# Beunboard_rev1.net
KiCad netlist of a schematic drawn in EAGLE
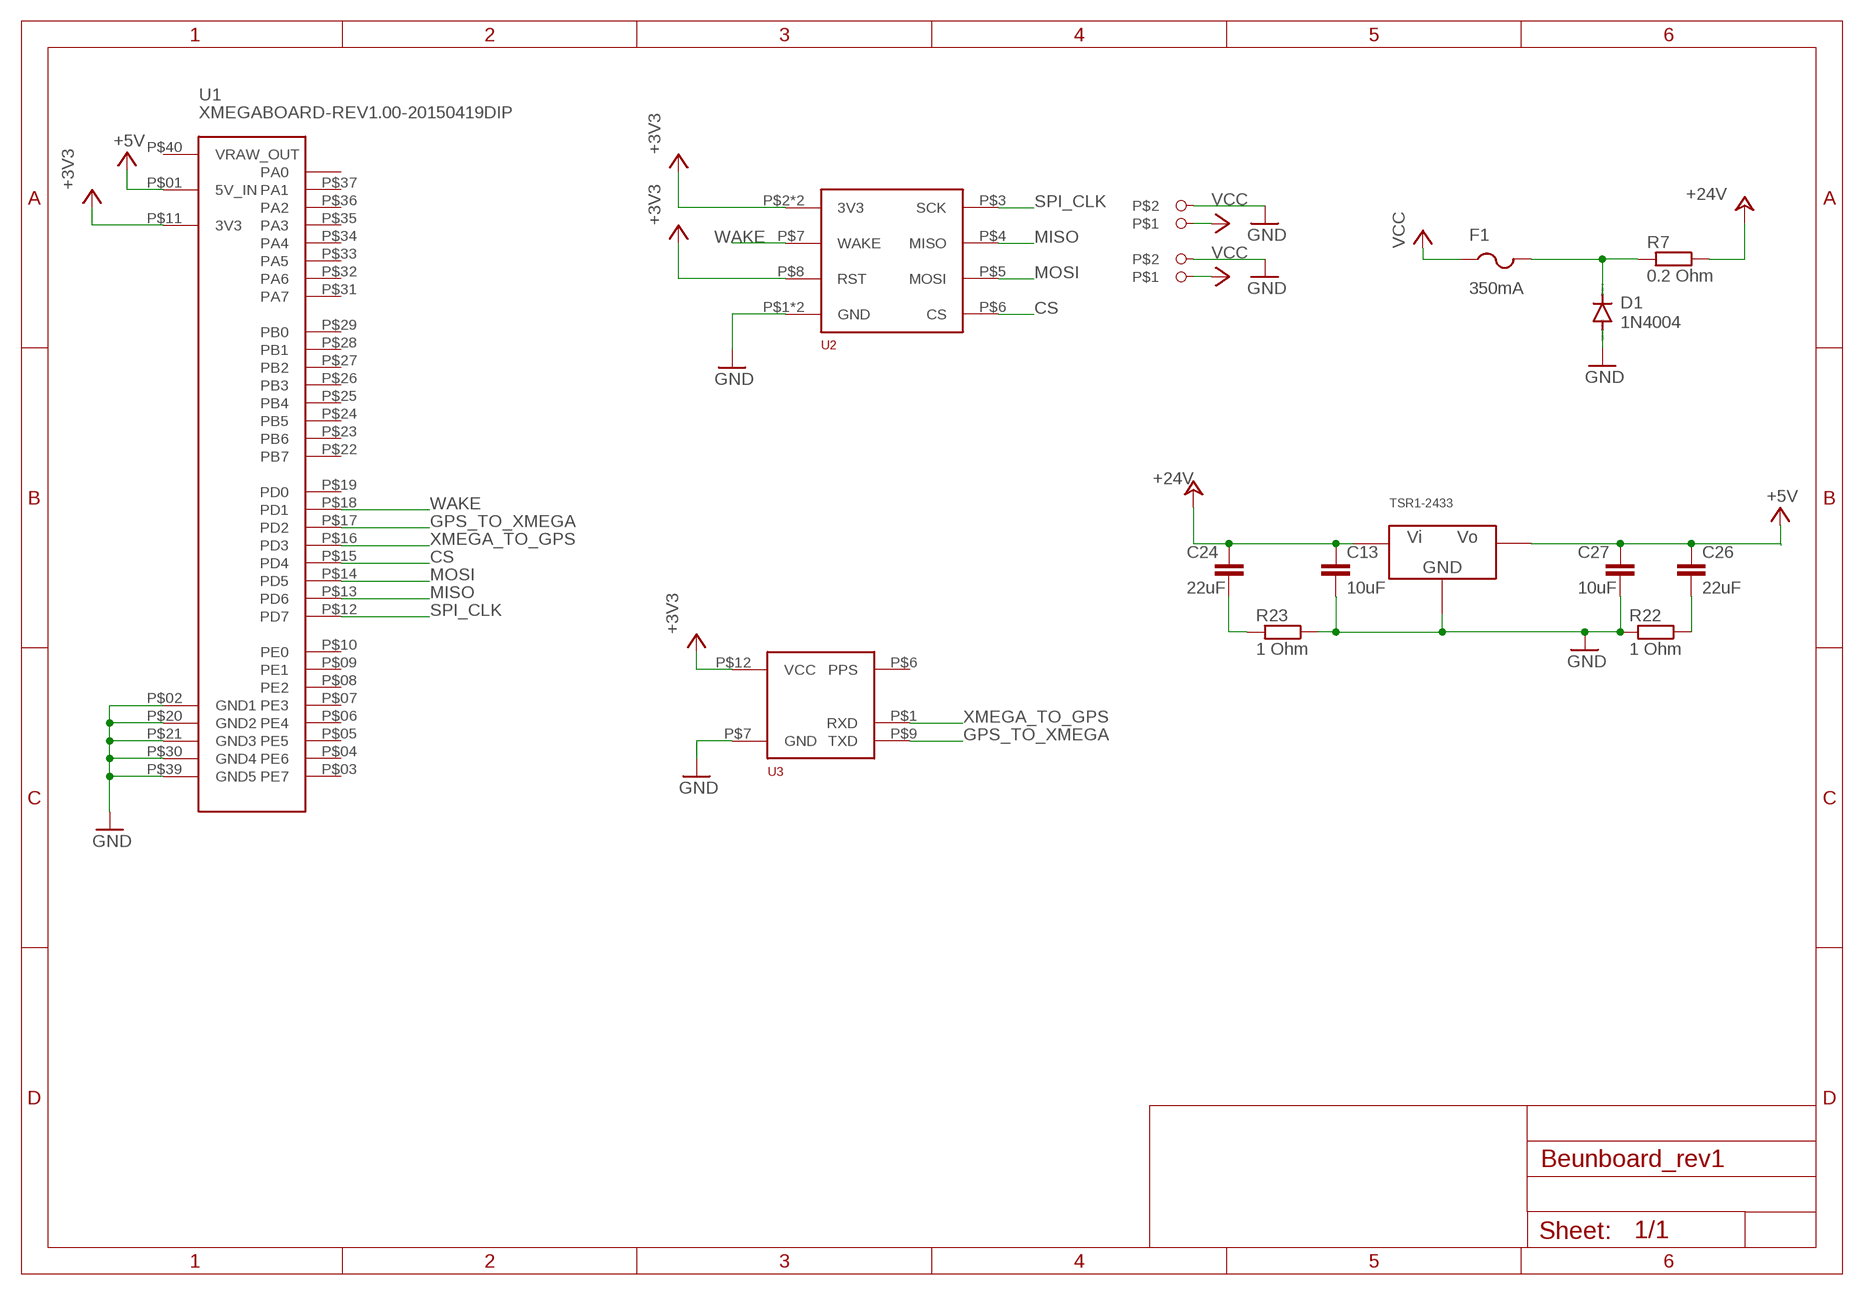
[diagram p0: schematic, sheet 1]

(export (version "E")
  (design (tool "Eeschema 10.0.6"))
  (components
    (comp (ref "C13")
      (value "10uF")
      (footprint "eagle-import:C1206")
      (libsource (lib "eagle-import") (part "C-EUC1206"))
    )
    (comp (ref "C24")
      (value "22uF")
      (footprint "eagle-import:C1206")
      (libsource (lib "eagle-import") (part "C-EUC1206"))
    )
    (comp (ref "C26")
      (value "22uF")
      (footprint "eagle-import:C1206")
      (libsource (lib "eagle-import") (part "C-EUC1206"))
    )
    (comp (ref "C27")
      (value "10uF")
      (footprint "eagle-import:C1206")
      (libsource (lib "eagle-import") (part "C-EUC1206"))
    )
    (comp (ref "D1")
      (value "1N4004")
      (footprint "eagle-import:DO41-10")
      (libsource (lib "eagle-import") (part "1N4004"))
    )
    (comp (ref "F1")
      (value "350mA")
      (footprint "eagle-import:R1206")
      (libsource (lib "eagle-import") (part "PTCFUSE-1206"))
    )
    (comp (ref "POWER1")
      (value "CON_3.81MM2_SIDE")
      (footprint "eagle-import:CON_3.81MM2_SIDE")
      (libsource (lib "eagle-import") (part "CON_3.81MM2_SIDE"))
    )
    (comp (ref "POWER2")
      (value "CON_3.81MM2_SIDE")
      (footprint "eagle-import:CON_3.81MM2_SIDE")
      (libsource (lib "eagle-import") (part "CON_3.81MM2_SIDE"))
    )
    (comp (ref "R7")
      (value "0.2 Ohm")
      (footprint "eagle-import:R0805")
      (libsource (lib "eagle-import") (part "R-EU_R0805"))
    )
    (comp (ref "R22")
      (value "1 Ohm")
      (footprint "eagle-import:R0805")
      (libsource (lib "eagle-import") (part "R-EU_R0805"))
    )
    (comp (ref "R23")
      (value "1 Ohm")
      (footprint "eagle-import:R0805")
      (libsource (lib "eagle-import") (part "R-EU_R0805"))
    )
    (comp (ref "TSR1-2433")
      (value "TSR1-2433")
      (footprint "eagle-import:TSR1-2433")
      (libsource (lib "eagle-import") (part "TSR1-2433"))
    )
    (comp (ref "U1")
      (value "XMEGABOARD-REV1.00-20150419DIP")
      (footprint "eagle-import:XMEGABOARD-REV1.00-20150419")
      (libsource (lib "eagle-import") (part "XMEGABOARD-REV1.00-20150419DIP"))
    )
    (comp (ref "U2")
      (value "SPARKFUN_BNO080SPARKFUN_BNO080")
      (footprint "eagle-import:SPARKFUN_BNO080")
      (libsource (lib "eagle-import") (part "SPARKFUN_BNO080SPARKFUN_BNO080"))
    )
    (comp (ref "U3")
      (value "NAVSPARK_MININAVSPARK_MINI")
      (footprint "eagle-import:NAVSPARK_MINI")
      (libsource (lib "eagle-import") (part "NAVSPARK_MININAVSPARK_MINI"))
    )
  )
  (nets
    (net (code "1") (name "+3V3") (class "Default")
      (node (ref "U1") (pin "P$11") (pinfunction "3V3_P$11") (pintype "bidirectional"))
      (node (ref "U2") (pin "P$18") (pinfunction "3V3_P$18") (pintype "bidirectional"))
      (node (ref "U2") (pin "P$2") (pinfunction "3V3_P$2") (pintype "bidirectional"))
      (node (ref "U2") (pin "P$8") (pinfunction "RST_P$8") (pintype "bidirectional"))
      (node (ref "U3") (pin "P$12") (pinfunction "VCC_P$12") (pintype "bidirectional"))
    )
    (net (code "2") (name "+5V") (class "Default")
      (node (ref "C26") (pin "1") (pinfunction "1_1") (pintype "passive"))
      (node (ref "C27") (pin "1") (pinfunction "1_1") (pintype "passive"))
      (node (ref "TSR1-2433") (pin "VO") (pinfunction "VO_VO") (pintype "bidirectional"))
      (node (ref "U1") (pin "P$01") (pinfunction "5V_IN_P$01") (pintype "bidirectional"))
    )
    (net (code "3") (name "+24V") (class "Default")
      (node (ref "C13") (pin "1") (pinfunction "1_1") (pintype "passive"))
      (node (ref "C24") (pin "1") (pinfunction "1_1") (pintype "passive"))
      (node (ref "R7") (pin "1") (pinfunction "1_1") (pintype "passive"))
      (node (ref "TSR1-2433") (pin "VI") (pinfunction "VI_VI") (pintype "bidirectional"))
    )
    (net (code "4") (name "/CS") (class "Default")
      (node (ref "U1") (pin "P$15") (pinfunction "PD4_P$15") (pintype "bidirectional"))
      (node (ref "U2") (pin "P$6") (pinfunction "CS_P$6") (pintype "bidirectional"))
    )
    (net (code "5") (name "/GPS_TO_XMEGA") (class "Default")
      (node (ref "U1") (pin "P$17") (pinfunction "PD2_P$17") (pintype "bidirectional"))
      (node (ref "U3") (pin "P$9") (pinfunction "TXD_P$9") (pintype "bidirectional"))
    )
    (net (code "6") (name "/MISO") (class "Default")
      (node (ref "U1") (pin "P$13") (pinfunction "PD6_P$13") (pintype "bidirectional"))
      (node (ref "U2") (pin "P$4") (pinfunction "MISO_P$4") (pintype "bidirectional"))
    )
    (net (code "7") (name "/MOSI") (class "Default")
      (node (ref "U1") (pin "P$14") (pinfunction "PD5_P$14") (pintype "bidirectional"))
      (node (ref "U2") (pin "P$5") (pinfunction "MOSI_P$5") (pintype "bidirectional"))
    )
    (net (code "8") (name "/SPI_CLK") (class "Default")
      (node (ref "U1") (pin "P$12") (pinfunction "PD7_P$12") (pintype "bidirectional"))
      (node (ref "U2") (pin "P$3") (pinfunction "SCK_P$3") (pintype "bidirectional"))
    )
    (net (code "9") (name "/WAKE") (class "Default")
      (node (ref "U1") (pin "P$18") (pinfunction "PD1_P$18") (pintype "bidirectional"))
      (node (ref "U2") (pin "P$7") (pinfunction "WAKE_P$7") (pintype "bidirectional"))
    )
    (net (code "10") (name "/XMEGA_TO_GPS") (class "Default")
      (node (ref "U1") (pin "P$16") (pinfunction "PD3_P$16") (pintype "bidirectional"))
      (node (ref "U3") (pin "P$1") (pinfunction "RXD_P$1") (pintype "bidirectional"))
    )
    (net (code "11") (name "GND") (class "Default")
      (node (ref "C13") (pin "2") (pinfunction "2_2") (pintype "passive"))
      (node (ref "C27") (pin "2") (pinfunction "2_2") (pintype "passive"))
      (node (ref "D1") (pin "A") (pinfunction "A_A") (pintype "passive"))
      (node (ref "POWER1") (pin "P$2") (pinfunction "P$2_P$2") (pintype "bidirectional"))
      (node (ref "POWER2") (pin "P$2") (pinfunction "P$2_P$2") (pintype "bidirectional"))
      (node (ref "R22") (pin "2") (pinfunction "2_2") (pintype "passive"))
      (node (ref "R23") (pin "1") (pinfunction "1_1") (pintype "passive"))
      (node (ref "TSR1-2433") (pin "GND") (pinfunction "GND_GND") (pintype "bidirectional"))
      (node (ref "U1") (pin "P$02") (pinfunction "GND1_P$02") (pintype "bidirectional"))
      (node (ref "U1") (pin "P$20") (pinfunction "GND2_P$20") (pintype "bidirectional"))
      (node (ref "U1") (pin "P$21") (pinfunction "GND3_P$21") (pintype "bidirectional"))
      (node (ref "U1") (pin "P$30") (pinfunction "GND4_P$30") (pintype "bidirectional"))
      (node (ref "U1") (pin "P$39") (pinfunction "GND5_P$39") (pintype "bidirectional"))
      (node (ref "U2") (pin "P$1") (pinfunction "GND_P$1") (pintype "bidirectional"))
      (node (ref "U2") (pin "P$17") (pinfunction "GND_P$17") (pintype "bidirectional"))
      (node (ref "U3") (pin "P$7") (pinfunction "GND_P$7") (pintype "bidirectional"))
    )
    (net (code "12") (name "Net-(C24-Pad2)") (class "Default")
      (node (ref "C24") (pin "2") (pinfunction "2_2") (pintype "passive"))
      (node (ref "R23") (pin "2") (pinfunction "2_2") (pintype "passive"))
    )
    (net (code "13") (name "Net-(C26-Pad2)") (class "Default")
      (node (ref "C26") (pin "2") (pinfunction "2_2") (pintype "passive"))
      (node (ref "R22") (pin "1") (pinfunction "1_1") (pintype "passive"))
    )
    (net (code "14") (name "Net-(D1-PadC)") (class "Default")
      (node (ref "D1") (pin "C") (pinfunction "C_C") (pintype "passive"))
      (node (ref "F1") (pin "2") (pinfunction "2_2") (pintype "passive"))
      (node (ref "R7") (pin "2") (pinfunction "2_2") (pintype "passive"))
    )
    (net (code "15") (name "VCC") (class "Default")
      (node (ref "F1") (pin "1") (pinfunction "1_1") (pintype "passive"))
      (node (ref "POWER1") (pin "P$1") (pinfunction "P$1_P$1") (pintype "bidirectional"))
      (node (ref "POWER2") (pin "P$1") (pinfunction "P$1_P$1") (pintype "bidirectional"))
    )
    (net (code "16") (name "unconnected-(U1-PA0-PadP$38)") (class "Default")
      (node (ref "U1") (pin "P$38") (pinfunction "PA0_P$38") (pintype "bidirectional"))
    )
    (net (code "17") (name "unconnected-(U1-PA1-PadP$37)") (class "Default")
      (node (ref "U1") (pin "P$37") (pinfunction "PA1_P$37") (pintype "bidirectional"))
    )
    (net (code "18") (name "unconnected-(U1-PA2-PadP$36)") (class "Default")
      (node (ref "U1") (pin "P$36") (pinfunction "PA2_P$36") (pintype "bidirectional"))
    )
    (net (code "19") (name "unconnected-(U1-PA3-PadP$35)") (class "Default")
      (node (ref "U1") (pin "P$35") (pinfunction "PA3_P$35") (pintype "bidirectional"))
    )
    (net (code "20") (name "unconnected-(U1-PA4-PadP$34)") (class "Default")
      (node (ref "U1") (pin "P$34") (pinfunction "PA4_P$34") (pintype "bidirectional"))
    )
    (net (code "21") (name "unconnected-(U1-PA5-PadP$33)") (class "Default")
      (node (ref "U1") (pin "P$33") (pinfunction "PA5_P$33") (pintype "bidirectional"))
    )
    (net (code "22") (name "unconnected-(U1-PA6-PadP$32)") (class "Default")
      (node (ref "U1") (pin "P$32") (pinfunction "PA6_P$32") (pintype "bidirectional"))
    )
    (net (code "23") (name "unconnected-(U1-PA7-PadP$31)") (class "Default")
      (node (ref "U1") (pin "P$31") (pinfunction "PA7_P$31") (pintype "bidirectional"))
    )
    (net (code "24") (name "unconnected-(U1-PB0-PadP$29)") (class "Default")
      (node (ref "U1") (pin "P$29") (pinfunction "PB0_P$29") (pintype "bidirectional"))
    )
    (net (code "25") (name "unconnected-(U1-PB1-PadP$28)") (class "Default")
      (node (ref "U1") (pin "P$28") (pinfunction "PB1_P$28") (pintype "bidirectional"))
    )
    (net (code "26") (name "unconnected-(U1-PB2-PadP$27)") (class "Default")
      (node (ref "U1") (pin "P$27") (pinfunction "PB2_P$27") (pintype "bidirectional"))
    )
    (net (code "27") (name "unconnected-(U1-PB3-PadP$26)") (class "Default")
      (node (ref "U1") (pin "P$26") (pinfunction "PB3_P$26") (pintype "bidirectional"))
    )
    (net (code "28") (name "unconnected-(U1-PB4-PadP$25)") (class "Default")
      (node (ref "U1") (pin "P$25") (pinfunction "PB4_P$25") (pintype "bidirectional"))
    )
    (net (code "29") (name "unconnected-(U1-PB5-PadP$24)") (class "Default")
      (node (ref "U1") (pin "P$24") (pinfunction "PB5_P$24") (pintype "bidirectional"))
    )
    (net (code "30") (name "unconnected-(U1-PB6-PadP$23)") (class "Default")
      (node (ref "U1") (pin "P$23") (pinfunction "PB6_P$23") (pintype "bidirectional"))
    )
    (net (code "31") (name "unconnected-(U1-PB7-PadP$22)") (class "Default")
      (node (ref "U1") (pin "P$22") (pinfunction "PB7_P$22") (pintype "bidirectional"))
    )
    (net (code "32") (name "unconnected-(U1-PD0-PadP$19)") (class "Default")
      (node (ref "U1") (pin "P$19") (pinfunction "PD0_P$19") (pintype "bidirectional"))
    )
    (net (code "33") (name "unconnected-(U1-PE0-PadP$10)") (class "Default")
      (node (ref "U1") (pin "P$10") (pinfunction "PE0_P$10") (pintype "bidirectional"))
    )
    (net (code "34") (name "unconnected-(U1-PE1-PadP$09)") (class "Default")
      (node (ref "U1") (pin "P$09") (pinfunction "PE1_P$09") (pintype "bidirectional"))
    )
    (net (code "35") (name "unconnected-(U1-PE2-PadP$08)") (class "Default")
      (node (ref "U1") (pin "P$08") (pinfunction "PE2_P$08") (pintype "bidirectional"))
    )
    (net (code "36") (name "unconnected-(U1-PE3-PadP$07)") (class "Default")
      (node (ref "U1") (pin "P$07") (pinfunction "PE3_P$07") (pintype "bidirectional"))
    )
    (net (code "37") (name "unconnected-(U1-PE4-PadP$06)") (class "Default")
      (node (ref "U1") (pin "P$06") (pinfunction "PE4_P$06") (pintype "bidirectional"))
    )
    (net (code "38") (name "unconnected-(U1-PE5-PadP$05)") (class "Default")
      (node (ref "U1") (pin "P$05") (pinfunction "PE5_P$05") (pintype "bidirectional"))
    )
    (net (code "39") (name "unconnected-(U1-PE6-PadP$04)") (class "Default")
      (node (ref "U1") (pin "P$04") (pinfunction "PE6_P$04") (pintype "bidirectional"))
    )
    (net (code "40") (name "unconnected-(U1-PE7-PadP$03)") (class "Default")
      (node (ref "U1") (pin "P$03") (pinfunction "PE7_P$03") (pintype "bidirectional"))
    )
    (net (code "41") (name "unconnected-(U1-VRAW_OUT-PadP$40)") (class "Default")
      (node (ref "U1") (pin "P$40") (pinfunction "VRAW_OUT_P$40") (pintype "bidirectional"))
    )
    (net (code "42") (name "unconnected-(U3-PPS-PadP$6)") (class "Default")
      (node (ref "U3") (pin "P$6") (pinfunction "PPS_P$6") (pintype "bidirectional"))
    )
  )
)
